# LEDS_SWITCHS.net
KiCad netlist of a schematic drawn in Altium Designer
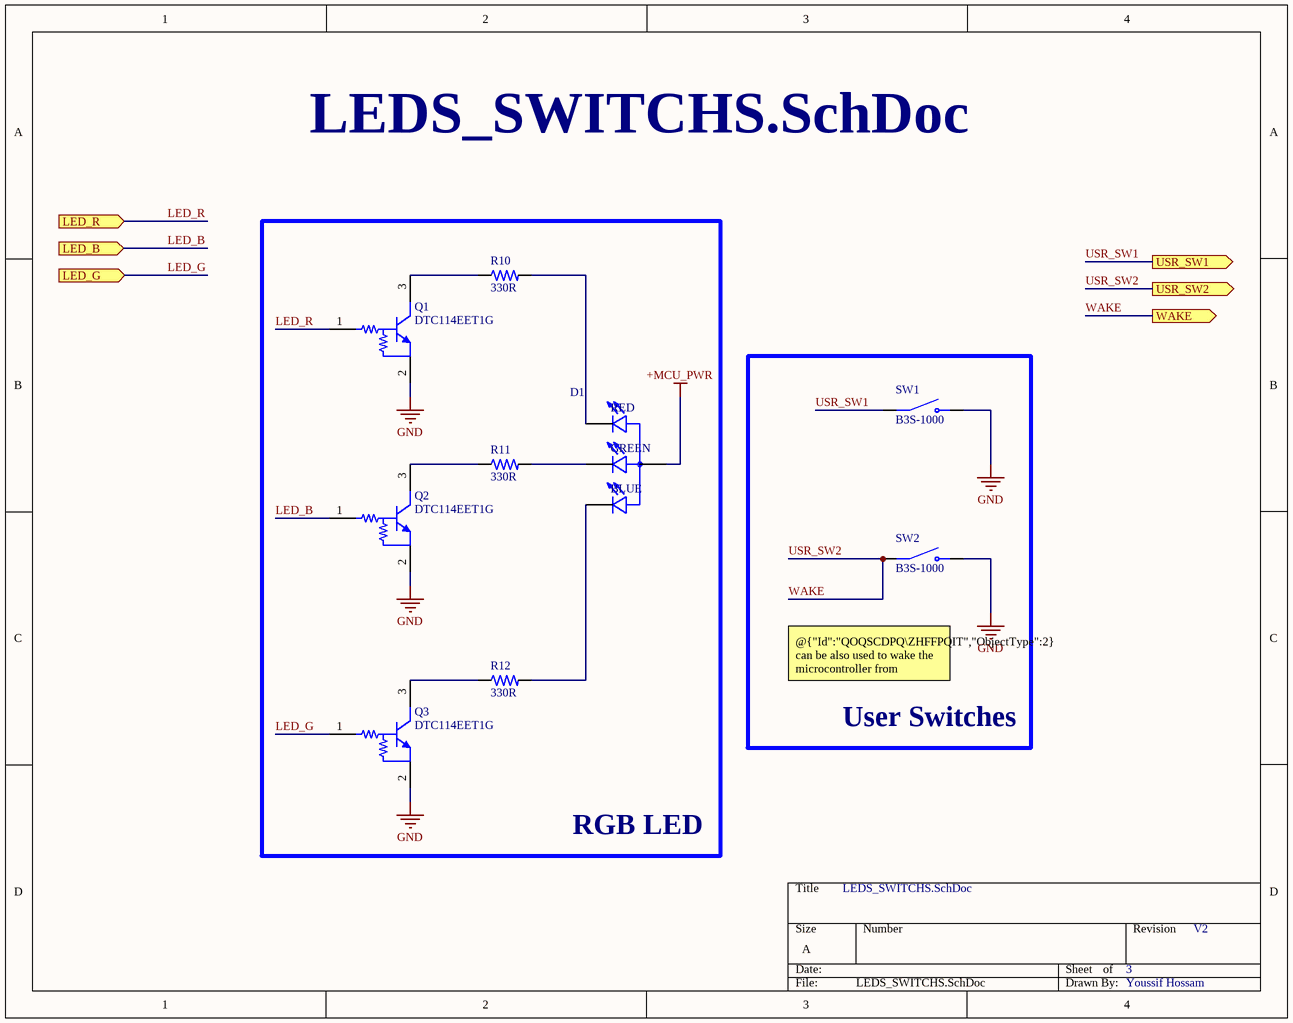
[diagram p0: LEDS_SWITCHS.SchDoc]

(export (version "E")
  (design (tool "Eeschema 10.0.6"))
  (components
    (comp (ref "D1")
      (value "CLMVC-FKA-CL1D1L71BB7C3C3")
      (footprint "LED_CLMVC-FKA-CL1D1L71BB7C3C3")
      (fields (field (name "MF") "{'manufacturer': u'CreeLED, Inc.'}"))
      (libsource (lib "Integrated_Library") (part "CLMVC-FKA-CL1D1L71BB7C3C3"))
    )
    (comp (ref "Q1")
      (value "DTC114EET1G")
      (footprint "ONSC-SC-75-3-463-01_V")
      (fields (field (name "MANUFACTURER") "On Semiconductor"))
      (libsource (lib "Integrated_Library") (part "CMP-0630-00210-1"))
    )
    (comp (ref "Q2")
      (value "DTC114EET1G")
      (footprint "ONSC-SC-75-3-463-01_V")
      (fields (field (name "MANUFACTURER") "On Semiconductor"))
      (libsource (lib "Integrated_Library") (part "CMP-0630-00210-1"))
    )
    (comp (ref "Q3")
      (value "DTC114EET1G")
      (footprint "ONSC-SC-75-3-463-01_V")
      (fields (field (name "MANUFACTURER") "On Semiconductor"))
      (libsource (lib "Integrated_Library") (part "CMP-0630-00210-1"))
    )
    (comp (ref "R10")
      (value "330R")
      (footprint "0402 RES")
      (fields
        (field (name "MANUFACTURER") "Vishay Dale")
        (field (name "MANUFACTURER PART NUMBER") "RCC0402330RFKED")
      )
      (libsource (lib "Integrated_Library") (part "0402 SMD Resistor"))
    )
    (comp (ref "R11")
      (value "330R")
      (footprint "0402 RES")
      (fields
        (field (name "MANUFACTURER") "Vishay Dale")
        (field (name "MANUFACTURER PART NUMBER") "RCC0402330RFKED")
      )
      (libsource (lib "Integrated_Library") (part "0402 SMD Resistor"))
    )
    (comp (ref "R12")
      (value "330R")
      (footprint "0402 RES")
      (fields
        (field (name "MANUFACTURER") "Vishay Dale")
        (field (name "MANUFACTURER PART NUMBER") "RCC0402330RFKED")
      )
      (libsource (lib "Integrated_Library") (part "0402 SMD Resistor"))
    )
    (comp (ref "SW1")
      (value "B3S-1000")
      (footprint "SW_B3S-1000")
      (description "Tactile Switch SPST-NO Top Actuated Surface Mount")
      (fields (field (name "MF") "Omron"))
      (libsource (lib "Integrated_Library") (part "B3S-1000"))
    )
    (comp (ref "SW2")
      (value "B3S-1000")
      (footprint "SW_B3S-1000")
      (description "Tactile Switch SPST-NO Top Actuated Surface Mount")
      (fields (field (name "MF") "Omron"))
      (libsource (lib "Integrated_Library") (part "B3S-1000"))
    )
  )
  (nets
    (net (code "1") (name "+MCU_PWR") (class "Default")
      (node (ref "D1") (pin "1") (pinfunction "A_1") (pintype "passive"))
    )
    (net (code "2") (name "/LED_B") (class "Default")
      (node (ref "Q2") (pin "1") (pinfunction "B_1") (pintype "passive"))
    )
    (net (code "3") (name "/LED_G") (class "Default")
      (node (ref "Q3") (pin "1") (pinfunction "B_1") (pintype "passive"))
    )
    (net (code "4") (name "/LED_R") (class "Default")
      (node (ref "Q1") (pin "1") (pinfunction "B_1") (pintype "passive"))
    )
    (net (code "5") (name "/USR_SW1") (class "Default")
      (node (ref "SW1") (pin "2") (pinfunction "COM_2") (pintype "passive"))
    )
    (net (code "6") (name "/USR_SW2") (class "Default")
      (node (ref "SW2") (pin "2") (pinfunction "COM_2") (pintype "passive"))
    )
    (net (code "7") (name "GND") (class "Default")
      (node (ref "Q1") (pin "2") (pinfunction "E_2") (pintype "passive"))
      (node (ref "Q2") (pin "2") (pinfunction "E_2") (pintype "passive"))
      (node (ref "Q3") (pin "2") (pinfunction "E_2") (pintype "passive"))
      (node (ref "SW1") (pin "4") (pinfunction "NO_4") (pintype "passive"))
      (node (ref "SW2") (pin "4") (pinfunction "NO_4") (pintype "passive"))
    )
    (net (code "8") (name "Net-(D1-B_C)") (class "Default")
      (node (ref "D1") (pin "2") (pinfunction "B_C_2") (pintype "passive"))
      (node (ref "R12") (pin "2") (pinfunction "2_2") (pintype "passive"))
    )
    (net (code "9") (name "Net-(D1-G_C)") (class "Default")
      (node (ref "D1") (pin "3") (pinfunction "G_C_3") (pintype "passive"))
      (node (ref "R11") (pin "2") (pinfunction "2_2") (pintype "passive"))
    )
    (net (code "10") (name "Net-(D1-R_C)") (class "Default")
      (node (ref "D1") (pin "4") (pinfunction "R_C_4") (pintype "passive"))
      (node (ref "R10") (pin "2") (pinfunction "2_2") (pintype "passive"))
    )
    (net (code "11") (name "Net-(Q1-C)") (class "Default")
      (node (ref "Q1") (pin "3") (pinfunction "C_3") (pintype "passive"))
      (node (ref "R10") (pin "1") (pinfunction "1_1") (pintype "passive"))
    )
    (net (code "12") (name "Net-(Q2-C)") (class "Default")
      (node (ref "Q2") (pin "3") (pinfunction "C_3") (pintype "passive"))
      (node (ref "R11") (pin "1") (pinfunction "1_1") (pintype "passive"))
    )
    (net (code "13") (name "Net-(Q3-C)") (class "Default")
      (node (ref "Q3") (pin "3") (pinfunction "C_3") (pintype "passive"))
      (node (ref "R12") (pin "1") (pinfunction "1_1") (pintype "passive"))
    )
  )
)
